# Main.net
KiCad netlist of a schematic drawn in Altium Designer
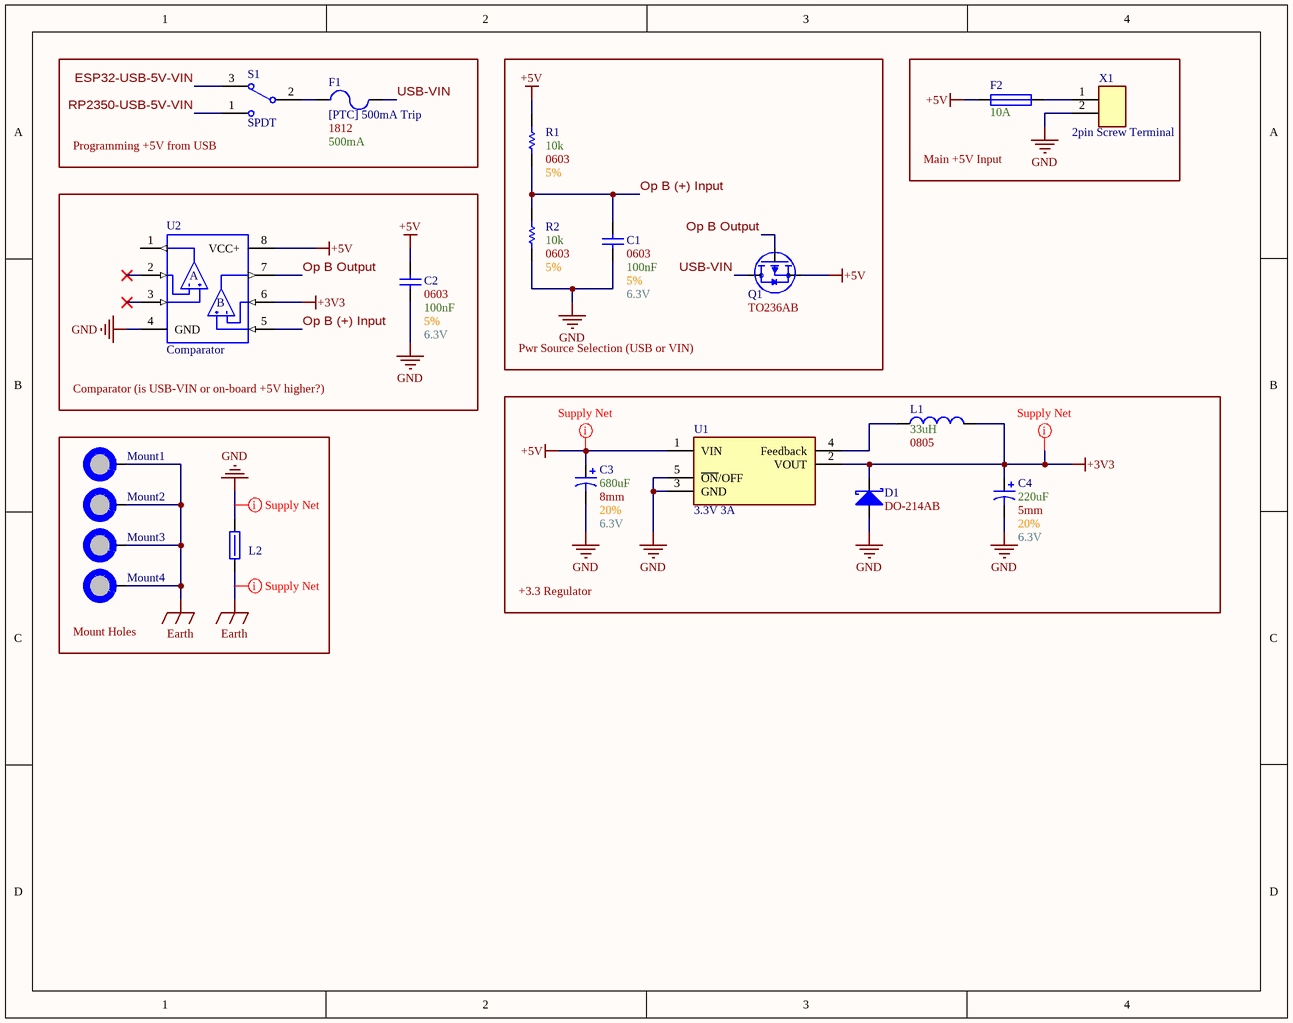
[diagram p0: Main.SchDoc]

(export (version "E")
  (design (tool "Eeschema 10.0.6"))
  (components
    (comp (ref "C1")
      (value "[Cap] SMD Nonpolarized")
      (footprint "[Cap] SMD 0603")
      (fields
        (field (name "SIZE PACKAGE") "0603")
        (field (name "CAPACITANCE") "100nF")
        (field (name "VOLTAGE") "6.3V")
        (field (name "TOLERANCE") "5%")
      )
      (libsource (lib "RADM Components") (part "[Cap] SMD Nonpolarized"))
    )
    (comp (ref "C2")
      (value "[Cap] SMD Nonpolarized")
      (footprint "[Cap] SMD 0603")
      (fields
        (field (name "SIZE PACKAGE") "0603")
        (field (name "CAPACITANCE") "100nF")
        (field (name "VOLTAGE") "6.3V")
        (field (name "TOLERANCE") "5%")
      )
      (libsource (lib "RADM Components") (part "[Cap] SMD Nonpolarized"))
    )
    (comp (ref "C3")
      (value "SMD Polarized")
      (footprint "[Cap] SMD Polarized, 8mm")
      (fields
        (field (name "TOLERANCE") "20%")
        (field (name "MAX VOLTAGE") "6.3V")
        (field (name "CAPACITANCE") "680uF")
        (field (name "DIAMETER") "8mm")
      )
      (libsource (lib "RADM Components") (part "[Cap] SMD Polarized"))
    )
    (comp (ref "C4")
      (value "SMD Polarized")
      (footprint "[Cap] SMD Polarized, 5mm")
      (fields
        (field (name "TOLERANCE") "20%")
        (field (name "MAX VOLTAGE") "6.3V")
        (field (name "CAPACITANCE") "220uF")
        (field (name "DIAMETER") "5mm")
      )
      (libsource (lib "RADM Components") (part "[Cap] SMD Polarized"))
    )
    (comp (ref "D1")
      (value "Schottky")
      (footprint "[Diode] SMD DO-214AB")
      (description "Generic")
      (fields (field (name "SIZE PACKAGE") "DO-214AB"))
      (libsource (lib "RADM Components") (part "[Diode] SMD Schottky"))
    )
    (comp (ref "F1")
      (value "[PTC] 500mA Trip")
      (footprint "[PTC] 500mA Trip")
      (description "MF-MSMF050-2")
      (fields (field (name "SIZE PACKAGE") "1812") (field (name "TRIP CURRENT") "500mA"))
      (libsource (lib "RADM Components") (part "[PTC] 500mA Trip"))
    )
    (comp (ref "F2")
      (value "Right-Angle")
      (footprint "[Fuse] Blade Right-Angle")
      (fields (field (name "AMPERAGE") "10A"))
      (libsource (lib "RADM Components") (part "[Fuse] Blade Right-Angle"))
    )
    (comp (ref "L1")
      (value "SMD Inductor")
      (footprint "[Inductor] SMD 0805")
      (fields (field (name "SIZE PACKAGE") "0805") (field (name "INDUCTANCE") "33uH"))
      (libsource (lib "RADM Components") (part "[Inductor] SMD Inductor"))
    )
    (comp (ref "L2")
      (value "652-MH2029-300Y")
      (footprint "[Ferrite] SMD Bead 0805 (1)")
      (libsource (lib "RADM Components") (part "[Ferrite] SMD Ferrite Bead (1)"))
    )
    (comp (ref "Mount1")
      (value "M3 Mount Hole")
      (footprint "[Mount] M3 Mount Hole")
      (description "Place at least 4.5mm from board edge. Plated.")
      (libsource (lib "RADM Connectors") (part "[Mount] M3 Mount Hole"))
    )
    (comp (ref "Mount2")
      (value "M3 Mount Hole")
      (footprint "[Mount] M3 Mount Hole")
      (description "Place at least 4.5mm from board edge. Plated.")
      (libsource (lib "RADM Connectors") (part "[Mount] M3 Mount Hole"))
    )
    (comp (ref "Mount3")
      (value "M3 Mount Hole")
      (footprint "[Mount] M3 Mount Hole")
      (description "Place at least 4.5mm from board edge. Plated.")
      (libsource (lib "RADM Connectors") (part "[Mount] M3 Mount Hole"))
    )
    (comp (ref "Mount4")
      (value "M3 Mount Hole")
      (footprint "[Mount] M3 Mount Hole")
      (description "Place at least 4.5mm from board edge. Plated.")
      (libsource (lib "RADM Connectors") (part "[Mount] M3 Mount Hole"))
    )
    (comp (ref "Q1")
      (value "PMV48XP")
      (footprint "[FET] P-Channel Mosfet")
      (fields (field (name "SIZE PACKAGE") "TO236AB"))
      (libsource (lib "RADM Components") (part "[FET] P-Channel MOSFET"))
    )
    (comp (ref "R1")
      (value "[Res] SMD Resistor")
      (footprint "[Res] SMD 0603")
      (description "Generic")
      (fields
        (field (name "RESISTANCE") "10k")
        (field (name "SIZE PACKAGE") "0603")
        (field (name "TOLERANCE") "5%")
      )
      (libsource (lib "RADM Components") (part "[Res] SMD Resistor"))
    )
    (comp (ref "R2")
      (value "[Res] SMD Resistor")
      (footprint "[Res] SMD 0603")
      (description "Generic")
      (fields
        (field (name "RESISTANCE") "10k")
        (field (name "SIZE PACKAGE") "0603")
        (field (name "TOLERANCE") "5%")
      )
      (libsource (lib "RADM Components") (part "[Res] SMD Resistor"))
    )
    (comp (ref "S1")
      (value "SPDT")
      (footprint "[Switch] SPDT")
      (libsource (lib "RADM Components") (part "[Switch] SPDT Switch"))
    )
    (comp (ref "U1")
      (value "3.3V 3A")
      (footprint "[Reg] 3V3 Regulator (4)")
      (description "3A")
      (libsource (lib "RADM Components") (part "[Reg] 3V3 Regulator (4)"))
    )
    (comp (ref "U2")
      (value "Comparator")
      (footprint "[IC] Dual Op-Ap")
      (description "LMV358IDGKR")
      (libsource (lib "RADM Components") (part "[IC] Dual Op-Amp"))
    )
    (comp (ref "X1")
      (value "2pin Screw Terminal")
      (footprint "[Screw Terminal] 2pin 5mm")
      (libsource (lib "RADM Connectors") (part "[Screw Terminal] 2pin"))
    )
  )
  (nets
    (net (code "1") (name "+3V3") (class "Default")
      (node (ref "C4") (pin "1") (pinfunction "1_1") (pintype "passive"))
      (node (ref "D1") (pin "1") (pinfunction "K_1") (pintype "power_in"))
      (node (ref "L1") (pin "2") (pinfunction "2_2") (pintype "passive"))
      (node (ref "U1") (pin "2") (pinfunction "VOUT_2") (pintype "passive"))
      (node (ref "U2") (pin "6") (pinfunction "2IN-_6") (pintype "input"))
    )
    (net (code "2") (name "+5V") (class "Default")
      (node (ref "C2") (pin "2") (pinfunction "2_2") (pintype "passive"))
      (node (ref "C3") (pin "1") (pinfunction "1_1") (pintype "passive"))
      (node (ref "F2") (pin "1") (pinfunction "1_1") (pintype "passive"))
      (node (ref "Q1") (pin "2") (pinfunction "S_2") (pintype "passive"))
      (node (ref "R1") (pin "2") (pinfunction "2_2") (pintype "passive"))
      (node (ref "U1") (pin "1") (pinfunction "VIN_1") (pintype "passive"))
      (node (ref "U2") (pin "8") (pinfunction "VCC+_8") (pintype "power_in"))
    )
    (net (code "3") (name "/ESP32-USB-5V-VIN") (class "Default")
      (node (ref "S1") (pin "3") (pinfunction "3_3") (pintype "passive"))
    )
    (net (code "4") (name "/Op B (+) Input") (class "Default")
      (node (ref "C1") (pin "2") (pinfunction "2_2") (pintype "passive"))
      (node (ref "R1") (pin "1") (pinfunction "1_1") (pintype "passive"))
      (node (ref "R2") (pin "2") (pinfunction "2_2") (pintype "passive"))
      (node (ref "U2") (pin "5") (pinfunction "2IN+_5") (pintype "input"))
    )
    (net (code "5") (name "/Op B Output") (class "Default")
      (node (ref "Q1") (pin "1") (pinfunction "G_1") (pintype "passive"))
      (node (ref "U2") (pin "7") (pinfunction "2OUT_7") (pintype "output"))
    )
    (net (code "6") (name "/RP2350-USB-5V-VIN") (class "Default")
      (node (ref "S1") (pin "1") (pinfunction "1_1") (pintype "passive"))
    )
    (net (code "7") (name "/USB-VIN") (class "Default")
      (node (ref "F1") (pin "2") (pinfunction "2_2") (pintype "passive"))
      (node (ref "Q1") (pin "3") (pinfunction "D_3") (pintype "passive"))
    )
    (net (code "8") (name "Earth") (class "Default")
      (node (ref "L2") (pin "1") (pinfunction "1_1") (pintype "passive"))
      (node (ref "Mount1") (pin "1") (pintype "power_in"))
      (node (ref "Mount2") (pin "1") (pintype "power_in"))
      (node (ref "Mount3") (pin "1") (pintype "power_in"))
      (node (ref "Mount4") (pin "1") (pintype "power_in"))
    )
    (net (code "9") (name "GND") (class "Default")
      (node (ref "C1") (pin "1") (pinfunction "1_1") (pintype "passive"))
      (node (ref "C2") (pin "1") (pinfunction "1_1") (pintype "passive"))
      (node (ref "C3") (pin "2") (pinfunction "2_2") (pintype "passive"))
      (node (ref "C4") (pin "2") (pinfunction "2_2") (pintype "passive"))
      (node (ref "D1") (pin "2") (pinfunction "A_2") (pintype "power_in"))
      (node (ref "L2") (pin "2") (pinfunction "2_2") (pintype "passive"))
      (node (ref "R2") (pin "1") (pinfunction "1_1") (pintype "passive"))
      (node (ref "U1") (pin "3") (pinfunction "GND_3") (pintype "passive"))
      (node (ref "U1") (pin "5") (pinfunction "~{ON}/OFF_5") (pintype "passive"))
      (node (ref "U2") (pin "4") (pinfunction "GND_4") (pintype "power_in"))
      (node (ref "X1") (pin "2") (pintype "power_in"))
    )
    (net (code "10") (name "Net-(F1-Pad1)") (class "Default")
      (node (ref "F1") (pin "1") (pinfunction "1_1") (pintype "passive"))
      (node (ref "S1") (pin "2") (pinfunction "2_2") (pintype "passive"))
    )
    (net (code "11") (name "Net-(F2-Pad2)") (class "Default")
      (node (ref "F2") (pin "2") (pinfunction "2_2") (pintype "passive"))
      (node (ref "X1") (pin "1") (pintype "power_in"))
    )
    (net (code "12") (name "Net-(U1-Feedback)") (class "Default")
      (node (ref "L1") (pin "1") (pinfunction "1_1") (pintype "passive"))
      (node (ref "U1") (pin "4") (pinfunction "Feedback_4") (pintype "passive"))
    )
    (net (code "13") (name "unconnected-(U2-1IN+-Pad3)") (class "Default")
      (node (ref "U2") (pin "3") (pinfunction "1IN+_3") (pintype "input+no_connect"))
    )
    (net (code "14") (name "unconnected-(U2-1IN--Pad2)") (class "Default")
      (node (ref "U2") (pin "2") (pinfunction "1IN-_2") (pintype "input+no_connect"))
    )
    (net (code "15") (name "unconnected-(U2-1OUT-Pad1)") (class "Default")
      (node (ref "U2") (pin "1") (pinfunction "1OUT_1") (pintype "output"))
    )
  )
)
